# ecoluz_scheme.net
KiCad netlist of a schematic drawn in EasyEDA
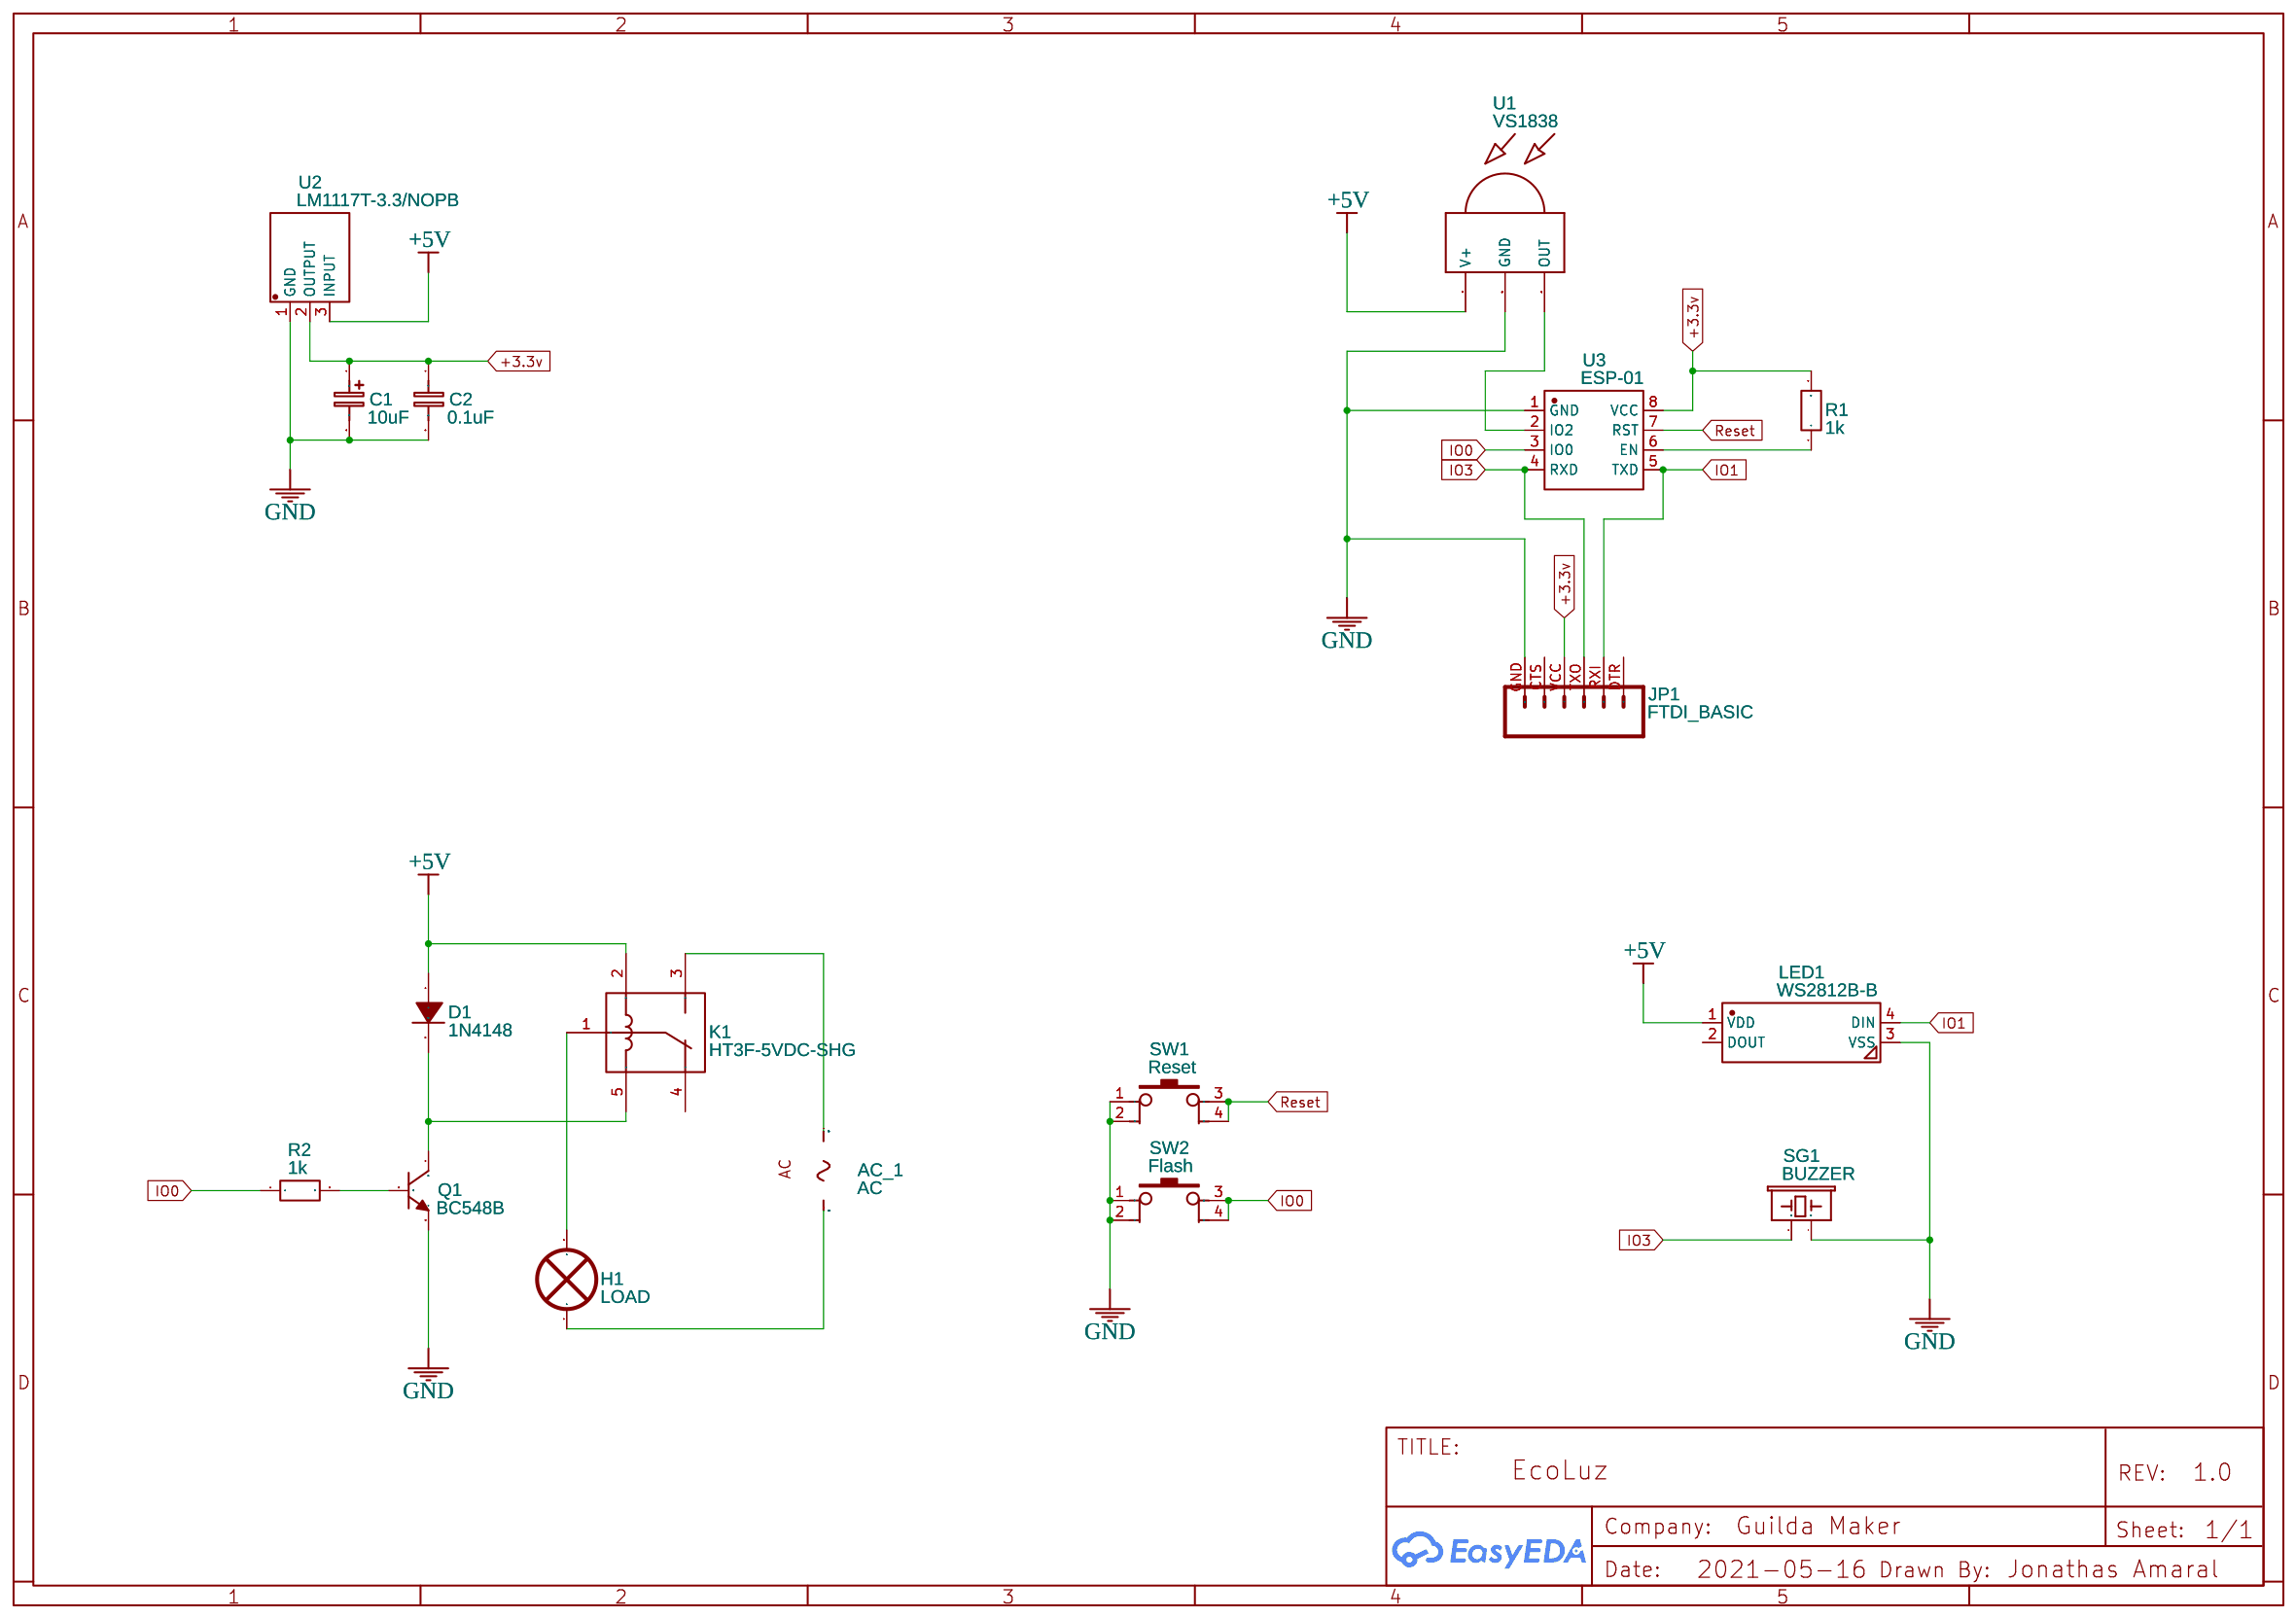
[diagram p0: schematic sheet]

(export (version "E")
  (design (tool "Eeschema 10.0.6"))
  (components
    (comp (ref "AC_1") (value "AC") (libsource (lib "") (part "AC")))
    (comp (ref "C1") (value "10uF") (libsource (lib "") (part "C_Tan_SMD_A_EU")))
    (comp (ref "C2") (value "0.1uF") (libsource (lib "") (part "C_RAD-0.1_EU")))
    (comp (ref "D1")
      (value "1N4148")
      (fields (field (name "BOM_Supplier Part") "C14516"))
      (libsource (lib "") (part "1N4148"))
    )
    (comp (ref "H1") (value "LOAD") (libsource (lib "") (part "BULB")))
    (comp (ref "JP1") (value "FTDI_BASIC") (libsource (lib "") (part "FTDI_BASIC")))
    (comp (ref "K1")
      (value "HT3F-5VDC-SHG")
      (fields (field (name "BOM_Supplier Part") "C129113"))
      (libsource (lib "") (part "HT3F-5VDC-SHG"))
    )
    (comp (ref "LED1")
      (value "WS2812B-B")
      (fields (field (name "BOM_Supplier Part") "C114586"))
      (libsource (lib "") (part "WS2812B-B"))
    )
    (comp (ref "Q1")
      (value "BC548B")
      (fields (field (name "BOM_Supplier Part") "C36611"))
      (libsource (lib "") (part "BC548B"))
    )
    (comp (ref "R1") (value "1k") (libsource (lib "") (part "R_0603_EU_1")))
    (comp (ref "R2") (value "1k") (libsource (lib "") (part "R_0603_EU")))
    (comp (ref "SG1") (value "BUZZER") (libsource (lib "") (part "BUZZER")))
    (comp (ref "SW1")
      (value "Reset")
      (fields
        (field (name "BOM_Manufacturer Part") "Switch6*6*11")
        (field (name "BOM_Supplier Part") "C91998")
      )
      (libsource (lib "") (part "Switch-SMD-6x6x11"))
    )
    (comp (ref "SW2")
      (value "Flash")
      (fields
        (field (name "BOM_Manufacturer Part") "Switch6*6*11")
        (field (name "BOM_Supplier Part") "C91998")
      )
      (libsource (lib "") (part "Switch-SMD-6x6x11"))
    )
    (comp (ref "U1") (value "VS1838") (libsource (lib "") (part "VS1838")))
    (comp (ref "U2")
      (value "LM1117T-3.3/NOPB")
      (fields (field (name "BOM_Supplier Part") "C201726"))
      (libsource (lib "") (part "LM1117T-3.3/NOPB"))
    )
    (comp (ref "U3")
      (value "ESP-01")
      (fields (field (name "BOM_Supplier Part") "C503581"))
      (libsource (lib "") (part "ESP-01"))
    )
  )
  (nets
    (net (code "1") (name "+3.3v") (class "Default")
      (node (ref "C1") (pin "1") (pinfunction "1_1") (pintype "unspecified"))
      (node (ref "C2") (pin "1") (pinfunction "1_1") (pintype "unspecified"))
      (node (ref "JP1") (pin "VCC") (pinfunction "4_VCC") (pintype "unspecified"))
      (node (ref "R1") (pin "2") (pinfunction "2_2") (pintype "unspecified"))
      (node (ref "U2") (pin "2") (pinfunction "OUTPUT_2") (pintype "unspecified"))
      (node (ref "U3") (pin "8") (pinfunction "VCC_8") (pintype "unspecified"))
    )
    (net (code "2") (name "+5V") (class "Default")
      (node (ref "D1") (pin "1") (pinfunction "A_1") (pintype "unspecified"))
      (node (ref "K1") (pin "2") (pinfunction "2_2") (pintype "unspecified"))
      (node (ref "LED1") (pin "1") (pinfunction "VDD_1") (pintype "unspecified"))
      (node (ref "U1") (pin "VCC") (pinfunction "V+_VCC") (pintype "unspecified"))
      (node (ref "U2") (pin "3") (pinfunction "INPUT_3") (pintype "unspecified"))
    )
    (net (code "3") (name "GND") (class "Default")
      (node (ref "C1") (pin "2") (pinfunction "2_2") (pintype "unspecified"))
      (node (ref "C2") (pin "2") (pinfunction "2_2") (pintype "unspecified"))
      (node (ref "JP1") (pin "GND") (pinfunction "6_GND") (pintype "unspecified"))
      (node (ref "LED1") (pin "3") (pinfunction "VSS_3") (pintype "unspecified"))
      (node (ref "Q1") (pin "3") (pinfunction "E_3") (pintype "unspecified"))
      (node (ref "SG1") (pin "-") (pinfunction "2_-") (pintype "unspecified"))
      (node (ref "SW1") (pin "1") (pinfunction "1_1") (pintype "input"))
      (node (ref "SW1") (pin "2") (pinfunction "2_2") (pintype "input"))
      (node (ref "SW2") (pin "1") (pinfunction "1_1") (pintype "input"))
      (node (ref "SW2") (pin "2") (pinfunction "2_2") (pintype "input"))
      (node (ref "U1") (pin "GND") (pinfunction "GND_GND") (pintype "unspecified"))
      (node (ref "U2") (pin "1") (pinfunction "GND_1") (pintype "unspecified"))
      (node (ref "U3") (pin "1") (pinfunction "GND_1") (pintype "unspecified"))
    )
    (net (code "4") (name "IO0") (class "Default")
      (node (ref "R2") (pin "1") (pinfunction "1_1") (pintype "unspecified"))
      (node (ref "SW2") (pin "3") (pinfunction "3_3") (pintype "input"))
      (node (ref "SW2") (pin "4") (pinfunction "4_4") (pintype "input"))
      (node (ref "U3") (pin "3") (pinfunction "IO0_3") (pintype "unspecified"))
    )
    (net (code "5") (name "IO1") (class "Default")
      (node (ref "JP1") (pin "RXI") (pinfunction "2_RXI") (pintype "unspecified"))
      (node (ref "LED1") (pin "4") (pinfunction "DIN_4") (pintype "unspecified"))
      (node (ref "U3") (pin "5") (pinfunction "TXD_5") (pintype "unspecified"))
    )
    (net (code "6") (name "IO3") (class "Default")
      (node (ref "JP1") (pin "TXO") (pinfunction "3_TXO") (pintype "unspecified"))
      (node (ref "SG1") (pin "+") (pinfunction "1_+") (pintype "unspecified"))
      (node (ref "U3") (pin "4") (pinfunction "RXD_4") (pintype "unspecified"))
    )
    (net (code "7") (name "Net-(AC_1-ANODE)") (class "Default")
      (node (ref "AC_1") (pin "A") (pinfunction "ANODE_A") (pintype "bidirectional"))
      (node (ref "K1") (pin "3") (pinfunction "3_3") (pintype "unspecified"))
    )
    (net (code "8") (name "Net-(AC_1-CATHODE)") (class "Default")
      (node (ref "AC_1") (pin "C") (pinfunction "CATHODE_C") (pintype "bidirectional"))
      (node (ref "H1") (pin "1") (pinfunction "1_1") (pintype "unspecified"))
    )
    (net (code "9") (name "Net-(D1-C)") (class "Default")
      (node (ref "D1") (pin "2") (pinfunction "C_2") (pintype "unspecified"))
      (node (ref "K1") (pin "5") (pinfunction "5_5") (pintype "unspecified"))
      (node (ref "Q1") (pin "1") (pinfunction "C_1") (pintype "unspecified"))
    )
    (net (code "10") (name "Net-(H1-Pad2)") (class "Default")
      (node (ref "H1") (pin "2") (pinfunction "2_2") (pintype "unspecified"))
      (node (ref "K1") (pin "1") (pinfunction "1_1") (pintype "unspecified"))
    )
    (net (code "11") (name "Net-(Q1-B)") (class "Default")
      (node (ref "Q1") (pin "2") (pinfunction "B_2") (pintype "unspecified"))
      (node (ref "R2") (pin "2") (pinfunction "2_2") (pintype "unspecified"))
    )
    (net (code "12") (name "Net-(U3-EN)") (class "Default")
      (node (ref "R1") (pin "1") (pinfunction "1_1") (pintype "unspecified"))
      (node (ref "U3") (pin "6") (pinfunction "EN_6") (pintype "unspecified"))
    )
    (net (code "13") (name "Net-(U3-IO2)") (class "Default")
      (node (ref "U1") (pin "OUT") (pinfunction "OUT_OUT") (pintype "unspecified"))
      (node (ref "U3") (pin "2") (pinfunction "IO2_2") (pintype "unspecified"))
    )
    (net (code "14") (name "Reset") (class "Default")
      (node (ref "SW1") (pin "3") (pinfunction "3_3") (pintype "input"))
      (node (ref "SW1") (pin "4") (pinfunction "4_4") (pintype "input"))
      (node (ref "U3") (pin "7") (pinfunction "RST_7") (pintype "unspecified"))
    )
    (net (code "15") (name "unconnected-(JP1-1-PadDTR)") (class "Default")
      (node (ref "JP1") (pin "DTR") (pinfunction "1_DTR") (pintype "unspecified"))
    )
    (net (code "16") (name "unconnected-(JP1-5-PadCTS)") (class "Default")
      (node (ref "JP1") (pin "CTS") (pinfunction "5_CTS") (pintype "unspecified"))
    )
    (net (code "17") (name "unconnected-(K1-Pad4)") (class "Default")
      (node (ref "K1") (pin "4") (pinfunction "4_4") (pintype "unspecified"))
    )
    (net (code "18") (name "unconnected-(LED1-DOUT-Pad2)") (class "Default")
      (node (ref "LED1") (pin "2") (pinfunction "DOUT_2") (pintype "unspecified"))
    )
  )
)
